# Memory.net
KiCad netlist of a schematic drawn in Altium Designer
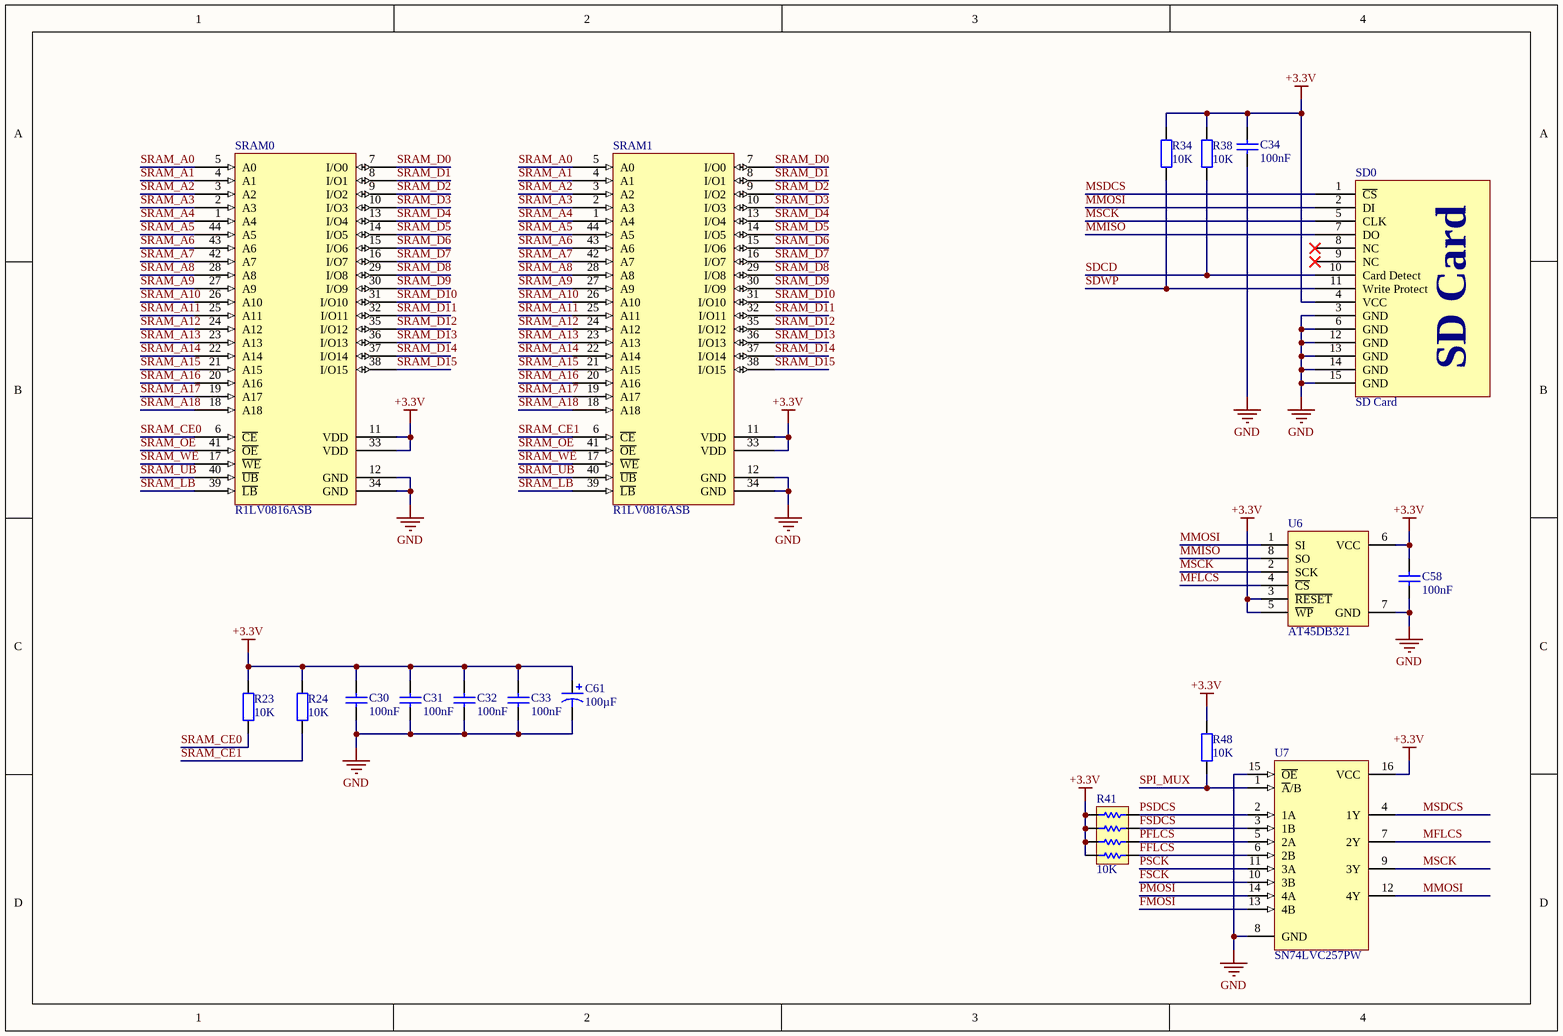
[diagram p0: Memory.SchDoc]

(export (version "E")
  (design (tool "Eeschema 10.0.6"))
  (components
    (comp (ref "C30")
      (value "100nF")
      (footprint "6-0805_n")
      (description "Capacitor")
      (fields (field (name "Comment") "Cap") (field (name "PUBLISHER") "Altium Limited"))
      (libsource (lib "Miscellaneous Devices") (part "Cap"))
    )
    (comp (ref "C31")
      (value "100nF")
      (footprint "6-0805_n")
      (description "Capacitor")
      (fields (field (name "Comment") "Cap") (field (name "PUBLISHER") "Altium Limited"))
      (libsource (lib "Miscellaneous Devices") (part "Cap"))
    )
    (comp (ref "C32")
      (value "100nF")
      (footprint "6-0805_n")
      (description "Capacitor")
      (fields (field (name "Comment") "Cap") (field (name "PUBLISHER") "Altium Limited"))
      (libsource (lib "Miscellaneous Devices") (part "Cap"))
    )
    (comp (ref "C33")
      (value "100nF")
      (footprint "6-0805_n")
      (description "Capacitor")
      (fields (field (name "Comment") "Cap") (field (name "PUBLISHER") "Altium Limited"))
      (libsource (lib "Miscellaneous Devices") (part "Cap"))
    )
    (comp (ref "C34")
      (value "100nF")
      (footprint "6-0805_n")
      (description "Capacitor")
      (fields (field (name "Comment") "Cap") (field (name "PUBLISHER") "Altium Limited"))
      (libsource (lib "Miscellaneous Devices") (part "Cap"))
    )
    (comp (ref "C58")
      (value "100nF")
      (footprint "6-0805_n")
      (description "Capacitor")
      (fields (field (name "Comment") "Cap") (field (name "PUBLISHER") "Altium Limited"))
      (libsource (lib "Miscellaneous Devices") (part "Cap"))
    )
    (comp (ref "C61")
      (value "100µF")
      (footprint "ECAP 6.3mm")
      (description "Polarized Capacitor (Surface Mount)")
      (fields (field (name "Comment") "Cap Pol3") (field (name "PUBLISHER") "Altium Limited"))
      (libsource (lib "Miscellaneous Devices") (part "Cap Pol3"))
    )
    (comp (ref "R23")
      (value "10K")
      (footprint "6-0805_N")
      (description "Resistor")
      (fields (field (name "Comment") "Res2") (field (name "PUBLISHER") "Altium Limited"))
      (libsource (lib "Miscellaneous Devices") (part "Res2"))
    )
    (comp (ref "R24")
      (value "10K")
      (footprint "6-0805_N")
      (description "Resistor")
      (fields (field (name "Comment") "Res2") (field (name "PUBLISHER") "Altium Limited"))
      (libsource (lib "Miscellaneous Devices") (part "Res2"))
    )
    (comp (ref "R34")
      (value "10K")
      (footprint "6-0805_N")
      (description "Resistor")
      (fields (field (name "Comment") "Res2") (field (name "PUBLISHER") "Altium Limited"))
      (libsource (lib "Miscellaneous Devices") (part "Res2"))
    )
    (comp (ref "R38")
      (value "10K")
      (footprint "6-0805_N")
      (description "Resistor")
      (fields (field (name "Comment") "Res2") (field (name "PUBLISHER") "Altium Limited"))
      (libsource (lib "Miscellaneous Devices") (part "Res2"))
    )
    (comp (ref "R41")
      (value "10K")
      (footprint "SMD 4 Resisor Network")
      (libsource (lib "eon_lib") (part "SMD 4 Resistor Network"))
    )
    (comp (ref "R48")
      (value "10K")
      (footprint "6-0805_N")
      (description "Resistor")
      (fields (field (name "Comment") "Res2") (field (name "PUBLISHER") "Altium Limited"))
      (libsource (lib "Miscellaneous Devices") (part "Res2"))
    )
    (comp (ref "SD0")
      (value "SD Card")
      (footprint "SD-Card Connector OK")
      (libsource (lib "Connectors") (part "SD Card Connector"))
    )
    (comp (ref "SRAM0")
      (value "R1LV0816ASB")
      (footprint "TSOP44")
      (description "8Mbit (512Kb x 16) Asynchron Static RAM")
      (libsource (lib "Memory") (part "R1LV0816ASB"))
    )
    (comp (ref "SRAM1")
      (value "R1LV0816ASB")
      (footprint "TSOP44")
      (description "8Mbit (512Kb x 16) Asynchron Static RAM")
      (libsource (lib "Memory") (part "R1LV0816ASB"))
    )
    (comp (ref "U6") (value "AT45DB321") (footprint "SOIC8") (libsource (lib "Memory") (part "AT45DB321D")))
    (comp (ref "U7")
      (value "SN74LVC257PW")
      (footprint "PW016_N")
      (description "Quadruple 2-Line to 1-Line Data Selector/Multiplexer with 3-State Outputs")
      (fields (field (name "PUBLISHER") "Altium Limited"))
      (libsource (lib "TI Logic Multiplexer") (part "SN74LVC257PW"))
    )
  )
  (nets
    (net (code "1") (name "+3.3V") (class "Default")
      (node (ref "C30") (pin "2") (pinfunction "2_2") (pintype "passive"))
      (node (ref "C31") (pin "2") (pinfunction "2_2") (pintype "passive"))
      (node (ref "C32") (pin "2") (pinfunction "2_2") (pintype "passive"))
      (node (ref "C33") (pin "2") (pinfunction "2_2") (pintype "passive"))
      (node (ref "C34") (pin "2") (pinfunction "2_2") (pintype "passive"))
      (node (ref "C58") (pin "2") (pinfunction "2_2") (pintype "passive"))
      (node (ref "C61") (pin "1") (pinfunction "1_1") (pintype "passive"))
      (node (ref "R23") (pin "1") (pinfunction "1_1") (pintype "passive"))
      (node (ref "R24") (pin "1") (pinfunction "1_1") (pintype "passive"))
      (node (ref "R34") (pin "1") (pinfunction "1_1") (pintype "passive"))
      (node (ref "R38") (pin "1") (pinfunction "1_1") (pintype "passive"))
      (node (ref "R41") (pin "1") (pinfunction "1_1") (pintype "passive"))
      (node (ref "R41") (pin "3") (pinfunction "3_3") (pintype "passive"))
      (node (ref "R41") (pin "5") (pinfunction "5_5") (pintype "passive"))
      (node (ref "R41") (pin "7") (pinfunction "7_7") (pintype "passive"))
      (node (ref "R48") (pin "1") (pinfunction "1_1") (pintype "passive"))
      (node (ref "SD0") (pin "4") (pinfunction "VCC_4") (pintype "passive"))
      (node (ref "SRAM0") (pin "11") (pinfunction "VDD_11") (pintype "power_in"))
      (node (ref "SRAM0") (pin "33") (pinfunction "VDD_33") (pintype "power_in"))
      (node (ref "SRAM1") (pin "11") (pinfunction "VDD_11") (pintype "power_in"))
      (node (ref "SRAM1") (pin "33") (pinfunction "VDD_33") (pintype "power_in"))
      (node (ref "U6") (pin "3") (pinfunction "~{RESET}_3") (pintype "passive"))
      (node (ref "U6") (pin "5") (pinfunction "~{WP}_5") (pintype "passive"))
      (node (ref "U6") (pin "6") (pinfunction "VCC_6") (pintype "passive"))
      (node (ref "U7") (pin "16") (pinfunction "VCC_16") (pintype "power_in"))
    )
    (net (code "2") (name "/FFLCS") (class "Default")
      (node (ref "R41") (pin "8") (pinfunction "8_8") (pintype "passive"))
      (node (ref "U7") (pin "6") (pinfunction "2B_6") (pintype "input"))
    )
    (net (code "3") (name "/FMOSI") (class "Default")
      (node (ref "U7") (pin "13") (pinfunction "4B_13") (pintype "input"))
    )
    (net (code "4") (name "/FSCK") (class "Default")
      (node (ref "U7") (pin "10") (pinfunction "3B_10") (pintype "input"))
    )
    (net (code "5") (name "/FSDCS") (class "Default")
      (node (ref "R41") (pin "4") (pinfunction "4_4") (pintype "passive"))
      (node (ref "U7") (pin "3") (pinfunction "1B_3") (pintype "input"))
    )
    (net (code "6") (name "/MFLCS") (class "Default")
      (node (ref "U6") (pin "4") (pinfunction "~{CS}_4") (pintype "passive"))
      (node (ref "U7") (pin "7") (pinfunction "2Y_7") (pintype "tri_state"))
    )
    (net (code "7") (name "/MMISO") (class "Default")
      (node (ref "SD0") (pin "7") (pinfunction "DO_7") (pintype "passive"))
      (node (ref "U6") (pin "8") (pinfunction "SO_8") (pintype "passive"))
    )
    (net (code "8") (name "/MMOSI") (class "Default")
      (node (ref "SD0") (pin "2") (pinfunction "DI_2") (pintype "passive"))
      (node (ref "U6") (pin "1") (pinfunction "SI_1") (pintype "passive"))
      (node (ref "U7") (pin "12") (pinfunction "4Y_12") (pintype "tri_state"))
    )
    (net (code "9") (name "/MSCK") (class "Default")
      (node (ref "SD0") (pin "5") (pinfunction "CLK_5") (pintype "passive"))
      (node (ref "U6") (pin "2") (pinfunction "SCK_2") (pintype "passive"))
      (node (ref "U7") (pin "9") (pinfunction "3Y_9") (pintype "tri_state"))
    )
    (net (code "10") (name "/MSDCS") (class "Default")
      (node (ref "SD0") (pin "1") (pinfunction "~{CS}_1") (pintype "passive"))
      (node (ref "U7") (pin "4") (pinfunction "1Y_4") (pintype "tri_state"))
    )
    (net (code "11") (name "/PFLCS") (class "Default")
      (node (ref "R41") (pin "6") (pinfunction "6_6") (pintype "passive"))
      (node (ref "U7") (pin "5") (pinfunction "2A_5") (pintype "input"))
    )
    (net (code "12") (name "/PMOSI") (class "Default")
      (node (ref "U7") (pin "14") (pinfunction "4A_14") (pintype "input"))
    )
    (net (code "13") (name "/PSCK") (class "Default")
      (node (ref "U7") (pin "11") (pinfunction "3A_11") (pintype "input"))
    )
    (net (code "14") (name "/PSDCS") (class "Default")
      (node (ref "R41") (pin "2") (pinfunction "2_2") (pintype "passive"))
      (node (ref "U7") (pin "2") (pinfunction "1A_2") (pintype "input"))
    )
    (net (code "15") (name "/SDCD") (class "Default")
      (node (ref "R38") (pin "2") (pinfunction "2_2") (pintype "passive"))
      (node (ref "SD0") (pin "10") (pinfunction "Card_Detect_10") (pintype "passive"))
    )
    (net (code "16") (name "/SDWP") (class "Default")
      (node (ref "R34") (pin "2") (pinfunction "2_2") (pintype "passive"))
      (node (ref "SD0") (pin "11") (pinfunction "Write_Protect_11") (pintype "passive"))
    )
    (net (code "17") (name "/SPI_MUX") (class "Default")
      (node (ref "R48") (pin "2") (pinfunction "2_2") (pintype "passive"))
      (node (ref "U7") (pin "1") (pinfunction "~{A}/B_1") (pintype "input"))
    )
    (net (code "18") (name "/SRAM_A0") (class "Default")
      (node (ref "SRAM0") (pin "5") (pinfunction "A0_5") (pintype "input"))
      (node (ref "SRAM1") (pin "5") (pinfunction "A0_5") (pintype "input"))
    )
    (net (code "19") (name "/SRAM_A1") (class "Default")
      (node (ref "SRAM0") (pin "4") (pinfunction "A1_4") (pintype "input"))
      (node (ref "SRAM1") (pin "4") (pinfunction "A1_4") (pintype "input"))
    )
    (net (code "20") (name "/SRAM_A2") (class "Default")
      (node (ref "SRAM0") (pin "3") (pinfunction "A2_3") (pintype "input"))
      (node (ref "SRAM1") (pin "3") (pinfunction "A2_3") (pintype "input"))
    )
    (net (code "21") (name "/SRAM_A3") (class "Default")
      (node (ref "SRAM0") (pin "2") (pinfunction "A3_2") (pintype "input"))
      (node (ref "SRAM1") (pin "2") (pinfunction "A3_2") (pintype "input"))
    )
    (net (code "22") (name "/SRAM_A4") (class "Default")
      (node (ref "SRAM0") (pin "1") (pinfunction "A4_1") (pintype "input"))
      (node (ref "SRAM1") (pin "1") (pinfunction "A4_1") (pintype "input"))
    )
    (net (code "23") (name "/SRAM_A5") (class "Default")
      (node (ref "SRAM0") (pin "44") (pinfunction "A5_44") (pintype "input"))
      (node (ref "SRAM1") (pin "44") (pinfunction "A5_44") (pintype "input"))
    )
    (net (code "24") (name "/SRAM_A6") (class "Default")
      (node (ref "SRAM0") (pin "43") (pinfunction "A6_43") (pintype "input"))
      (node (ref "SRAM1") (pin "43") (pinfunction "A6_43") (pintype "input"))
    )
    (net (code "25") (name "/SRAM_A7") (class "Default")
      (node (ref "SRAM0") (pin "42") (pinfunction "A7_42") (pintype "input"))
      (node (ref "SRAM1") (pin "42") (pinfunction "A7_42") (pintype "input"))
    )
    (net (code "26") (name "/SRAM_A8") (class "Default")
      (node (ref "SRAM0") (pin "28") (pinfunction "A8_28") (pintype "input"))
      (node (ref "SRAM1") (pin "28") (pinfunction "A8_28") (pintype "input"))
    )
    (net (code "27") (name "/SRAM_A9") (class "Default")
      (node (ref "SRAM0") (pin "27") (pinfunction "A9_27") (pintype "input"))
      (node (ref "SRAM1") (pin "27") (pinfunction "A9_27") (pintype "input"))
    )
    (net (code "28") (name "/SRAM_A10") (class "Default")
      (node (ref "SRAM0") (pin "26") (pinfunction "A10_26") (pintype "input"))
      (node (ref "SRAM1") (pin "26") (pinfunction "A10_26") (pintype "input"))
    )
    (net (code "29") (name "/SRAM_A11") (class "Default")
      (node (ref "SRAM0") (pin "25") (pinfunction "A11_25") (pintype "input"))
      (node (ref "SRAM1") (pin "25") (pinfunction "A11_25") (pintype "input"))
    )
    (net (code "30") (name "/SRAM_A12") (class "Default")
      (node (ref "SRAM0") (pin "24") (pinfunction "A12_24") (pintype "input"))
      (node (ref "SRAM1") (pin "24") (pinfunction "A12_24") (pintype "input"))
    )
    (net (code "31") (name "/SRAM_A13") (class "Default")
      (node (ref "SRAM0") (pin "23") (pinfunction "A13_23") (pintype "input"))
      (node (ref "SRAM1") (pin "23") (pinfunction "A13_23") (pintype "input"))
    )
    (net (code "32") (name "/SRAM_A14") (class "Default")
      (node (ref "SRAM0") (pin "22") (pinfunction "A14_22") (pintype "input"))
      (node (ref "SRAM1") (pin "22") (pinfunction "A14_22") (pintype "input"))
    )
    (net (code "33") (name "/SRAM_A15") (class "Default")
      (node (ref "SRAM0") (pin "21") (pinfunction "A15_21") (pintype "input"))
      (node (ref "SRAM1") (pin "21") (pinfunction "A15_21") (pintype "input"))
    )
    (net (code "34") (name "/SRAM_A16") (class "Default")
      (node (ref "SRAM0") (pin "20") (pinfunction "A16_20") (pintype "input"))
      (node (ref "SRAM1") (pin "20") (pinfunction "A16_20") (pintype "input"))
    )
    (net (code "35") (name "/SRAM_A17") (class "Default")
      (node (ref "SRAM0") (pin "19") (pinfunction "A17_19") (pintype "input"))
      (node (ref "SRAM1") (pin "19") (pinfunction "A17_19") (pintype "input"))
    )
    (net (code "36") (name "/SRAM_A18") (class "Default")
      (node (ref "SRAM0") (pin "18") (pinfunction "A18_18") (pintype "input"))
      (node (ref "SRAM1") (pin "18") (pinfunction "A18_18") (pintype "input"))
    )
    (net (code "37") (name "/SRAM_CE0") (class "Default")
      (node (ref "R23") (pin "2") (pinfunction "2_2") (pintype "passive"))
      (node (ref "SRAM0") (pin "6") (pinfunction "~{CE}_6") (pintype "input"))
    )
    (net (code "38") (name "/SRAM_CE1") (class "Default")
      (node (ref "R24") (pin "2") (pinfunction "2_2") (pintype "passive"))
      (node (ref "SRAM1") (pin "6") (pinfunction "~{CE}_6") (pintype "input"))
    )
    (net (code "39") (name "/SRAM_D0") (class "Default")
      (node (ref "SRAM0") (pin "7") (pinfunction "I/O0_7") (pintype "bidirectional"))
      (node (ref "SRAM1") (pin "7") (pinfunction "I/O0_7") (pintype "bidirectional"))
    )
    (net (code "40") (name "/SRAM_D1") (class "Default")
      (node (ref "SRAM0") (pin "8") (pinfunction "I/O1_8") (pintype "bidirectional"))
      (node (ref "SRAM1") (pin "8") (pinfunction "I/O1_8") (pintype "bidirectional"))
    )
    (net (code "41") (name "/SRAM_D2") (class "Default")
      (node (ref "SRAM0") (pin "9") (pinfunction "I/O2_9") (pintype "bidirectional"))
      (node (ref "SRAM1") (pin "9") (pinfunction "I/O2_9") (pintype "bidirectional"))
    )
    (net (code "42") (name "/SRAM_D3") (class "Default")
      (node (ref "SRAM0") (pin "10") (pinfunction "I/O3_10") (pintype "bidirectional"))
      (node (ref "SRAM1") (pin "10") (pinfunction "I/O3_10") (pintype "bidirectional"))
    )
    (net (code "43") (name "/SRAM_D4") (class "Default")
      (node (ref "SRAM0") (pin "13") (pinfunction "I/O4_13") (pintype "bidirectional"))
      (node (ref "SRAM1") (pin "13") (pinfunction "I/O4_13") (pintype "bidirectional"))
    )
    (net (code "44") (name "/SRAM_D5") (class "Default")
      (node (ref "SRAM0") (pin "14") (pinfunction "I/O5_14") (pintype "bidirectional"))
      (node (ref "SRAM1") (pin "14") (pinfunction "I/O5_14") (pintype "bidirectional"))
    )
    (net (code "45") (name "/SRAM_D6") (class "Default")
      (node (ref "SRAM0") (pin "15") (pinfunction "I/O6_15") (pintype "bidirectional"))
      (node (ref "SRAM1") (pin "15") (pinfunction "I/O6_15") (pintype "bidirectional"))
    )
    (net (code "46") (name "/SRAM_D7") (class "Default")
      (node (ref "SRAM0") (pin "16") (pinfunction "I/O7_16") (pintype "bidirectional"))
      (node (ref "SRAM1") (pin "16") (pinfunction "I/O7_16") (pintype "bidirectional"))
    )
    (net (code "47") (name "/SRAM_D8") (class "Default")
      (node (ref "SRAM0") (pin "29") (pinfunction "I/O8_29") (pintype "bidirectional"))
      (node (ref "SRAM1") (pin "29") (pinfunction "I/O8_29") (pintype "bidirectional"))
    )
    (net (code "48") (name "/SRAM_D9") (class "Default")
      (node (ref "SRAM0") (pin "30") (pinfunction "I/O9_30") (pintype "bidirectional"))
      (node (ref "SRAM1") (pin "30") (pinfunction "I/O9_30") (pintype "bidirectional"))
    )
    (net (code "49") (name "/SRAM_D10") (class "Default")
      (node (ref "SRAM0") (pin "31") (pinfunction "I/O10_31") (pintype "bidirectional"))
      (node (ref "SRAM1") (pin "31") (pinfunction "I/O10_31") (pintype "bidirectional"))
    )
    (net (code "50") (name "/SRAM_D11") (class "Default")
      (node (ref "SRAM0") (pin "32") (pinfunction "I/O11_32") (pintype "bidirectional"))
      (node (ref "SRAM1") (pin "32") (pinfunction "I/O11_32") (pintype "bidirectional"))
    )
    (net (code "51") (name "/SRAM_D12") (class "Default")
      (node (ref "SRAM0") (pin "35") (pinfunction "I/O12_35") (pintype "bidirectional"))
      (node (ref "SRAM1") (pin "35") (pinfunction "I/O12_35") (pintype "bidirectional"))
    )
    (net (code "52") (name "/SRAM_D13") (class "Default")
      (node (ref "SRAM0") (pin "36") (pinfunction "I/O13_36") (pintype "bidirectional"))
      (node (ref "SRAM1") (pin "36") (pinfunction "I/O13_36") (pintype "bidirectional"))
    )
    (net (code "53") (name "/SRAM_D14") (class "Default")
      (node (ref "SRAM0") (pin "37") (pinfunction "I/O14_37") (pintype "bidirectional"))
      (node (ref "SRAM1") (pin "37") (pinfunction "I/O14_37") (pintype "bidirectional"))
    )
    (net (code "54") (name "/SRAM_D15") (class "Default")
      (node (ref "SRAM0") (pin "38") (pinfunction "I/O15_38") (pintype "bidirectional"))
      (node (ref "SRAM1") (pin "38") (pinfunction "I/O15_38") (pintype "bidirectional"))
    )
    (net (code "55") (name "/SRAM_LB") (class "Default")
      (node (ref "SRAM0") (pin "39") (pinfunction "~{LB}_39") (pintype "input"))
      (node (ref "SRAM1") (pin "39") (pinfunction "~{LB}_39") (pintype "input"))
    )
    (net (code "56") (name "/SRAM_OE") (class "Default")
      (node (ref "SRAM0") (pin "41") (pinfunction "~{OE}_41") (pintype "input"))
      (node (ref "SRAM1") (pin "41") (pinfunction "~{OE}_41") (pintype "input"))
    )
    (net (code "57") (name "/SRAM_UB") (class "Default")
      (node (ref "SRAM0") (pin "40") (pinfunction "~{UB}_40") (pintype "input"))
      (node (ref "SRAM1") (pin "40") (pinfunction "~{UB}_40") (pintype "input"))
    )
    (net (code "58") (name "/SRAM_WE") (class "Default")
      (node (ref "SRAM0") (pin "17") (pinfunction "~{WE}_17") (pintype "input"))
      (node (ref "SRAM1") (pin "17") (pinfunction "~{WE}_17") (pintype "input"))
    )
    (net (code "59") (name "GND") (class "Default")
      (node (ref "C30") (pin "1") (pinfunction "1_1") (pintype "passive"))
      (node (ref "C31") (pin "1") (pinfunction "1_1") (pintype "passive"))
      (node (ref "C32") (pin "1") (pinfunction "1_1") (pintype "passive"))
      (node (ref "C33") (pin "1") (pinfunction "1_1") (pintype "passive"))
      (node (ref "C34") (pin "1") (pinfunction "1_1") (pintype "passive"))
      (node (ref "C58") (pin "1") (pinfunction "1_1") (pintype "passive"))
      (node (ref "C61") (pin "2") (pinfunction "2_2") (pintype "passive"))
      (node (ref "SD0") (pin "12") (pinfunction "GND_12") (pintype "passive"))
      (node (ref "SD0") (pin "13") (pinfunction "GND_13") (pintype "passive"))
      (node (ref "SD0") (pin "14") (pinfunction "GND_14") (pintype "passive"))
      (node (ref "SD0") (pin "15") (pinfunction "GND_15") (pintype "passive"))
      (node (ref "SD0") (pin "3") (pinfunction "GND_3") (pintype "passive"))
      (node (ref "SD0") (pin "6") (pinfunction "GND_6") (pintype "passive"))
      (node (ref "SRAM0") (pin "12") (pinfunction "GND_12") (pintype "power_in"))
      (node (ref "SRAM0") (pin "34") (pinfunction "GND_34") (pintype "power_in"))
      (node (ref "SRAM1") (pin "12") (pinfunction "GND_12") (pintype "power_in"))
      (node (ref "SRAM1") (pin "34") (pinfunction "GND_34") (pintype "power_in"))
      (node (ref "U6") (pin "7") (pinfunction "GND_7") (pintype "passive"))
      (node (ref "U7") (pin "15") (pinfunction "~{OE}_15") (pintype "input"))
      (node (ref "U7") (pin "8") (pinfunction "GND_8") (pintype "power_in"))
    )
    (net (code "60") (name "unconnected-(SD0-NC-Pad8)") (class "Default")
      (node (ref "SD0") (pin "8") (pinfunction "NC_8") (pintype "passive+no_connect"))
    )
    (net (code "61") (name "unconnected-(SD0-NC-Pad9)") (class "Default")
      (node (ref "SD0") (pin "9") (pinfunction "NC_9") (pintype "passive+no_connect"))
    )
  )
)
